# PowerManagement_uC_v2.net
KiCad netlist of a schematic drawn in Altium Designer
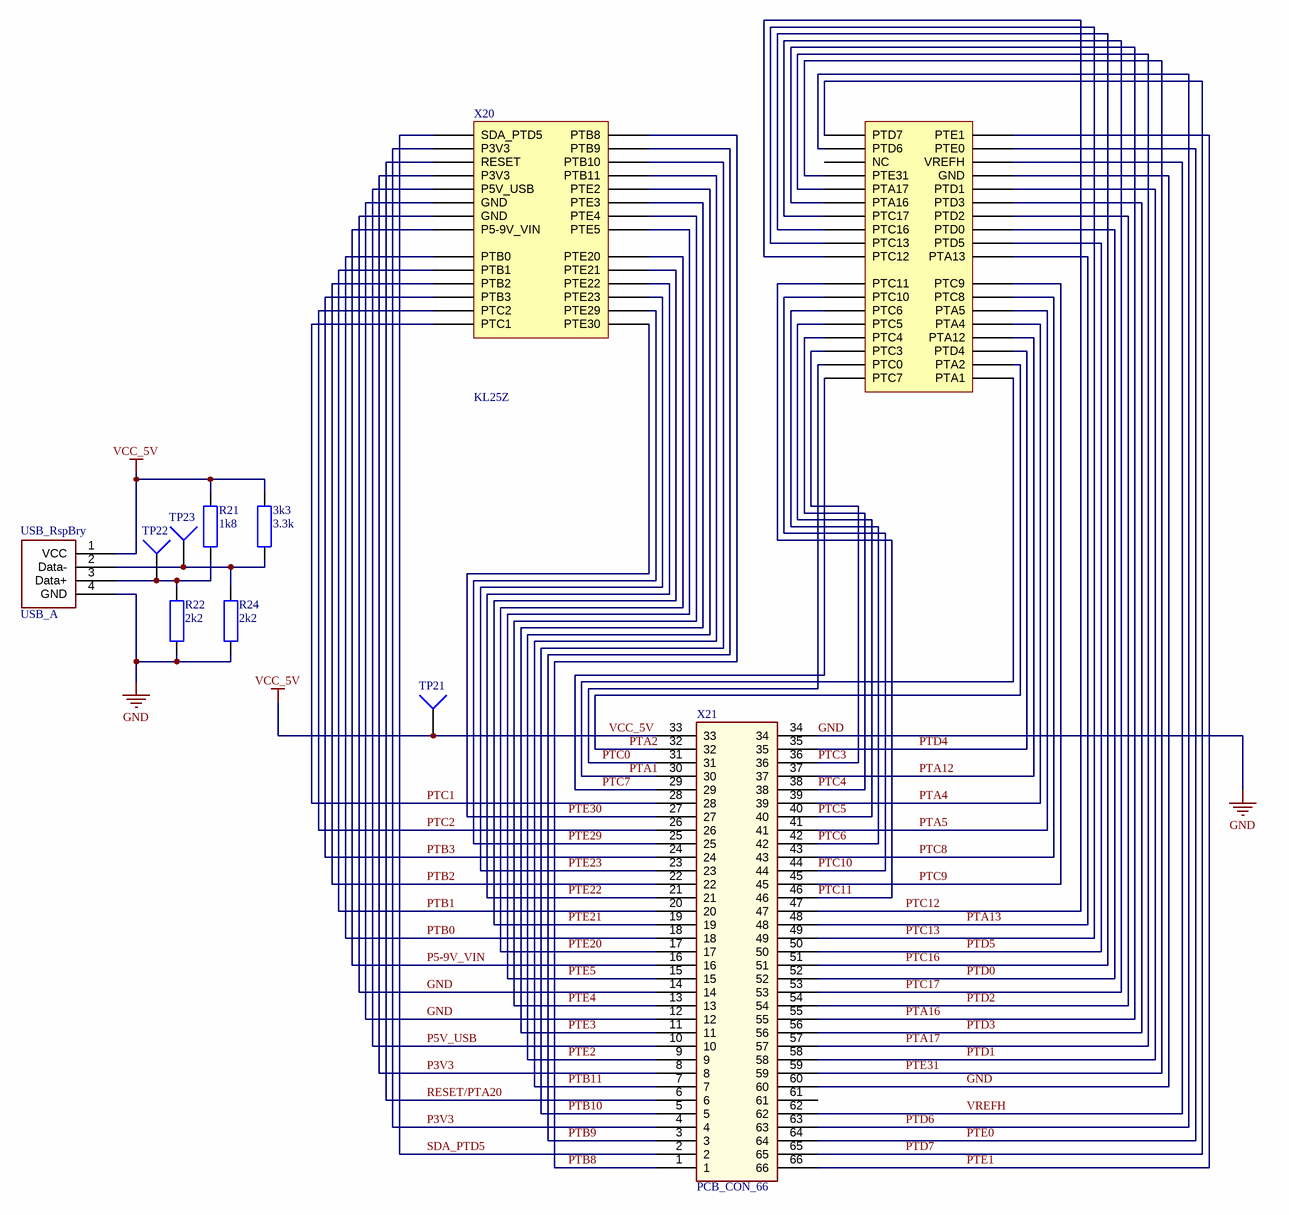
[diagram p0: PowerManagement_uC_v2.SchDoc]

(export (version "E")
  (design (tool "Eeschema 10.0.6"))
  (components
    (comp (ref "3k3")
      (value "3.3k")
      (footprint "0805")
      (description "Normaler Widerstand")
      (libsource (lib "SPICE_HSLU") (part "R?"))
    )
    (comp (ref "R21")
      (value "1k8")
      (footprint "0805")
      (description "Normaler Widerstand")
      (libsource (lib "SPICE_HSLU") (part "R?"))
    )
    (comp (ref "R22")
      (value "2k2")
      (footprint "0805")
      (description "Normaler Widerstand")
      (libsource (lib "SPICE_HSLU") (part "R?"))
    )
    (comp (ref "R24")
      (value "2k2")
      (footprint "0805")
      (description "Normaler Widerstand")
      (libsource (lib "SPICE_HSLU") (part "R?"))
    )
    (comp (ref "TP21")
      (value "~")
      (footprint "PIN1")
      (fields (field (name "PUBLISHER") "Altium Limited"))
      (libsource (lib "Miscellaneous Connectors") (part "Socket"))
    )
    (comp (ref "TP22")
      (value "~")
      (footprint "PIN1")
      (fields (field (name "PUBLISHER") "Altium Limited"))
      (libsource (lib "Miscellaneous Connectors") (part "Socket"))
    )
    (comp (ref "TP23")
      (value "~")
      (footprint "PIN1")
      (fields (field (name "PUBLISHER") "Altium Limited"))
      (libsource (lib "Miscellaneous Connectors") (part "Socket"))
    )
    (comp (ref "USB_RspBry") (value "USB_A") (footprint "USB_A") (libsource (lib "PREN2Lib") (part "USB_A")))
    (comp (ref "X20")
      (value "KL25Z")
      (footprint "Freedom KL25Z Headerarray")
      (description "FRDM KL25Z Shield")
      (libsource (lib "FreedomKL25Z") (part "Freedom KL25Z Header"))
    )
    (comp (ref "X21")
      (value "PCB_CON_66")
      (footprint "PCB_CON_66_PLUG")
      (description "Connects a PCB with another. This scheme is either jack or plug, depends on footprint")
      (libsource (lib "PREN2Lib") (part "PCB_CON_66"))
    )
  )
  (nets
    (net (code "1") (name "/P3V3") (class "Default")
      (node (ref "X20") (pin "3") (pinfunction "P3V3_3") (pintype "passive"))
      (node (ref "X20") (pin "7") (pinfunction "P3V3_7") (pintype "passive"))
      (node (ref "X21") (pin "4") (pinfunction "4_4") (pintype "passive"))
      (node (ref "X21") (pin "8") (pinfunction "8_8") (pintype "passive"))
    )
    (net (code "2") (name "/P5-9V_VIN") (class "Default")
      (node (ref "X20") (pin "15") (pinfunction "P5-9V_VIN_15") (pintype "passive"))
      (node (ref "X21") (pin "16") (pinfunction "16_16") (pintype "passive"))
    )
    (net (code "3") (name "/P5V_USB") (class "Default")
      (node (ref "X20") (pin "9") (pinfunction "P5V_USB_9") (pintype "passive"))
      (node (ref "X21") (pin "10") (pinfunction "10_10") (pintype "passive"))
    )
    (net (code "4") (name "/PTA1") (class "Default")
      (node (ref "X20") (pin "64") (pinfunction "PTA1_64") (pintype "passive"))
      (node (ref "X21") (pin "30") (pinfunction "30_30") (pintype "passive"))
    )
    (net (code "5") (name "/PTA2") (class "Default")
      (node (ref "X20") (pin "62") (pinfunction "PTA2_62") (pintype "passive"))
      (node (ref "X21") (pin "32") (pinfunction "32_32") (pintype "passive"))
    )
    (net (code "6") (name "/PTA4") (class "Default")
      (node (ref "X20") (pin "56") (pinfunction "PTA4_56") (pintype "passive"))
      (node (ref "X21") (pin "39") (pinfunction "39_39") (pintype "passive"))
    )
    (net (code "7") (name "/PTA5") (class "Default")
      (node (ref "X20") (pin "54") (pinfunction "PTA5_54") (pintype "passive"))
      (node (ref "X21") (pin "41") (pinfunction "41_41") (pintype "passive"))
    )
    (net (code "8") (name "/PTA12") (class "Default")
      (node (ref "X20") (pin "58") (pinfunction "PTA12_58") (pintype "passive"))
      (node (ref "X21") (pin "37") (pinfunction "37_37") (pintype "passive"))
    )
    (net (code "9") (name "/PTA13") (class "Default")
      (node (ref "X20") (pin "48") (pinfunction "PTA13_48") (pintype "passive"))
      (node (ref "X21") (pin "48") (pinfunction "48_48") (pintype "passive"))
    )
    (net (code "10") (name "/PTA16") (class "Default")
      (node (ref "X20") (pin "39") (pinfunction "PTA16_39") (pintype "passive"))
      (node (ref "X21") (pin "55") (pinfunction "55_55") (pintype "passive"))
    )
    (net (code "11") (name "/PTA17") (class "Default")
      (node (ref "X20") (pin "37") (pinfunction "PTA17_37") (pintype "passive"))
      (node (ref "X21") (pin "57") (pinfunction "57_57") (pintype "passive"))
    )
    (net (code "12") (name "/PTB0") (class "Default")
      (node (ref "X20") (pin "17") (pinfunction "PTB0_17") (pintype "passive"))
      (node (ref "X21") (pin "18") (pinfunction "18_18") (pintype "passive"))
    )
    (net (code "13") (name "/PTB1") (class "Default")
      (node (ref "X20") (pin "19") (pinfunction "PTB1_19") (pintype "passive"))
      (node (ref "X21") (pin "20") (pinfunction "20_20") (pintype "passive"))
    )
    (net (code "14") (name "/PTB2") (class "Default")
      (node (ref "X20") (pin "21") (pinfunction "PTB2_21") (pintype "passive"))
      (node (ref "X21") (pin "22") (pinfunction "22_22") (pintype "passive"))
    )
    (net (code "15") (name "/PTB3") (class "Default")
      (node (ref "X20") (pin "23") (pinfunction "PTB3_23") (pintype "passive"))
      (node (ref "X21") (pin "24") (pinfunction "24_24") (pintype "passive"))
    )
    (net (code "16") (name "/PTB8") (class "Default")
      (node (ref "X20") (pin "2") (pinfunction "PTB8_2") (pintype "passive"))
      (node (ref "X21") (pin "1") (pinfunction "1_1") (pintype "passive"))
    )
    (net (code "17") (name "/PTB9") (class "Default")
      (node (ref "X20") (pin "4") (pinfunction "PTB9_4") (pintype "passive"))
      (node (ref "X21") (pin "3") (pinfunction "3_3") (pintype "passive"))
    )
    (net (code "18") (name "/PTB10") (class "Default")
      (node (ref "X20") (pin "6") (pinfunction "PTB10_6") (pintype "passive"))
      (node (ref "X21") (pin "5") (pinfunction "5_5") (pintype "passive"))
    )
    (net (code "19") (name "/PTB11") (class "Default")
      (node (ref "X20") (pin "8") (pinfunction "PTB11_8") (pintype "passive"))
      (node (ref "X21") (pin "7") (pinfunction "7_7") (pintype "passive"))
    )
    (net (code "20") (name "/PTC0") (class "Default")
      (node (ref "X20") (pin "61") (pinfunction "PTC0_61") (pintype "passive"))
      (node (ref "X21") (pin "31") (pinfunction "31_31") (pintype "passive"))
    )
    (net (code "21") (name "/PTC1") (class "Default")
      (node (ref "X20") (pin "27") (pinfunction "PTC1_27") (pintype "passive"))
      (node (ref "X21") (pin "28") (pinfunction "28_28") (pintype "passive"))
    )
    (net (code "22") (name "/PTC2") (class "Default")
      (node (ref "X20") (pin "25") (pinfunction "PTC2_25") (pintype "passive"))
      (node (ref "X21") (pin "26") (pinfunction "26_26") (pintype "passive"))
    )
    (net (code "23") (name "/PTC3") (class "Default")
      (node (ref "X20") (pin "59") (pinfunction "PTC3_59") (pintype "passive"))
      (node (ref "X21") (pin "36") (pinfunction "36_36") (pintype "passive"))
    )
    (net (code "24") (name "/PTC4") (class "Default")
      (node (ref "X20") (pin "57") (pinfunction "PTC4_57") (pintype "passive"))
      (node (ref "X21") (pin "38") (pinfunction "38_38") (pintype "passive"))
    )
    (net (code "25") (name "/PTC5") (class "Default")
      (node (ref "X20") (pin "55") (pinfunction "PTC5_55") (pintype "passive"))
      (node (ref "X21") (pin "40") (pinfunction "40_40") (pintype "passive"))
    )
    (net (code "26") (name "/PTC6") (class "Default")
      (node (ref "X20") (pin "53") (pinfunction "PTC6_53") (pintype "passive"))
      (node (ref "X21") (pin "42") (pinfunction "42_42") (pintype "passive"))
    )
    (net (code "27") (name "/PTC7") (class "Default")
      (node (ref "X20") (pin "63") (pinfunction "PTC7_63") (pintype "passive"))
      (node (ref "X21") (pin "29") (pinfunction "29_29") (pintype "passive"))
    )
    (net (code "28") (name "/PTC8") (class "Default")
      (node (ref "X20") (pin "52") (pinfunction "PTC8_52") (pintype "passive"))
      (node (ref "X21") (pin "43") (pinfunction "43_43") (pintype "passive"))
    )
    (net (code "29") (name "/PTC9") (class "Default")
      (node (ref "X20") (pin "50") (pinfunction "PTC9_50") (pintype "passive"))
      (node (ref "X21") (pin "45") (pinfunction "45_45") (pintype "passive"))
    )
    (net (code "30") (name "/PTC10") (class "Default")
      (node (ref "X20") (pin "51") (pinfunction "PTC10_51") (pintype "passive"))
      (node (ref "X21") (pin "44") (pinfunction "44_44") (pintype "passive"))
    )
    (net (code "31") (name "/PTC11") (class "Default")
      (node (ref "X20") (pin "49") (pinfunction "PTC11_49") (pintype "passive"))
      (node (ref "X21") (pin "46") (pinfunction "46_46") (pintype "passive"))
    )
    (net (code "32") (name "/PTC12") (class "Default")
      (node (ref "X20") (pin "47") (pinfunction "PTC12_47") (pintype "passive"))
      (node (ref "X21") (pin "47") (pinfunction "47_47") (pintype "passive"))
    )
    (net (code "33") (name "/PTC13") (class "Default")
      (node (ref "X20") (pin "45") (pinfunction "PTC13_45") (pintype "passive"))
      (node (ref "X21") (pin "49") (pinfunction "49_49") (pintype "passive"))
    )
    (net (code "34") (name "/PTC16") (class "Default")
      (node (ref "X20") (pin "43") (pinfunction "PTC16_43") (pintype "passive"))
      (node (ref "X21") (pin "51") (pinfunction "51_51") (pintype "passive"))
    )
    (net (code "35") (name "/PTC17") (class "Default")
      (node (ref "X20") (pin "41") (pinfunction "PTC17_41") (pintype "passive"))
      (node (ref "X21") (pin "53") (pinfunction "53_53") (pintype "passive"))
    )
    (net (code "36") (name "/PTD0") (class "Default")
      (node (ref "X20") (pin "44") (pinfunction "PTD0_44") (pintype "passive"))
      (node (ref "X21") (pin "52") (pinfunction "52_52") (pintype "passive"))
    )
    (net (code "37") (name "/PTD1") (class "Default")
      (node (ref "X20") (pin "38") (pinfunction "PTD1_38") (pintype "passive"))
      (node (ref "X21") (pin "58") (pinfunction "58_58") (pintype "passive"))
    )
    (net (code "38") (name "/PTD2") (class "Default")
      (node (ref "X20") (pin "42") (pinfunction "PTD2_42") (pintype "passive"))
      (node (ref "X21") (pin "54") (pinfunction "54_54") (pintype "passive"))
    )
    (net (code "39") (name "/PTD3") (class "Default")
      (node (ref "X20") (pin "40") (pinfunction "PTD3_40") (pintype "passive"))
      (node (ref "X21") (pin "56") (pinfunction "56_56") (pintype "passive"))
    )
    (net (code "40") (name "/PTD4") (class "Default")
      (node (ref "X20") (pin "60") (pinfunction "PTD4_60") (pintype "passive"))
      (node (ref "X21") (pin "35") (pinfunction "35_35") (pintype "passive"))
    )
    (net (code "41") (name "/PTD5") (class "Default")
      (node (ref "X20") (pin "46") (pinfunction "PTD5_46") (pintype "passive"))
      (node (ref "X21") (pin "50") (pinfunction "50_50") (pintype "passive"))
    )
    (net (code "42") (name "/PTD6") (class "Default")
      (node (ref "X20") (pin "31") (pinfunction "PTD6_31") (pintype "passive"))
      (node (ref "X21") (pin "63") (pinfunction "63_63") (pintype "passive"))
    )
    (net (code "43") (name "/PTD7") (class "Default")
      (node (ref "X20") (pin "29") (pinfunction "PTD7_29") (pintype "passive"))
      (node (ref "X21") (pin "65") (pinfunction "65_65") (pintype "passive"))
    )
    (net (code "44") (name "/PTE0") (class "Default")
      (node (ref "X20") (pin "32") (pinfunction "PTE0_32") (pintype "passive"))
      (node (ref "X21") (pin "64") (pinfunction "64_64") (pintype "passive"))
    )
    (net (code "45") (name "/PTE1") (class "Default")
      (node (ref "X20") (pin "30") (pinfunction "PTE1_30") (pintype "passive"))
      (node (ref "X21") (pin "66") (pinfunction "66_66") (pintype "passive"))
    )
    (net (code "46") (name "/PTE2") (class "Default")
      (node (ref "X20") (pin "10") (pinfunction "PTE2_10") (pintype "passive"))
      (node (ref "X21") (pin "9") (pinfunction "9_9") (pintype "passive"))
    )
    (net (code "47") (name "/PTE3") (class "Default")
      (node (ref "X20") (pin "12") (pinfunction "PTE3_12") (pintype "passive"))
      (node (ref "X21") (pin "11") (pinfunction "11_11") (pintype "passive"))
    )
    (net (code "48") (name "/PTE4") (class "Default")
      (node (ref "X20") (pin "14") (pinfunction "PTE4_14") (pintype "passive"))
      (node (ref "X21") (pin "13") (pinfunction "13_13") (pintype "passive"))
    )
    (net (code "49") (name "/PTE5") (class "Default")
      (node (ref "X20") (pin "16") (pinfunction "PTE5_16") (pintype "passive"))
      (node (ref "X21") (pin "15") (pinfunction "15_15") (pintype "passive"))
    )
    (net (code "50") (name "/PTE20") (class "Default")
      (node (ref "X20") (pin "18") (pinfunction "PTE20_18") (pintype "passive"))
      (node (ref "X21") (pin "17") (pinfunction "17_17") (pintype "passive"))
    )
    (net (code "51") (name "/PTE21") (class "Default")
      (node (ref "X20") (pin "20") (pinfunction "PTE21_20") (pintype "passive"))
      (node (ref "X21") (pin "19") (pinfunction "19_19") (pintype "passive"))
    )
    (net (code "52") (name "/PTE22") (class "Default")
      (node (ref "X20") (pin "22") (pinfunction "PTE22_22") (pintype "passive"))
      (node (ref "X21") (pin "21") (pinfunction "21_21") (pintype "passive"))
    )
    (net (code "53") (name "/PTE23") (class "Default")
      (node (ref "X20") (pin "24") (pinfunction "PTE23_24") (pintype "passive"))
      (node (ref "X21") (pin "23") (pinfunction "23_23") (pintype "passive"))
    )
    (net (code "54") (name "/PTE29") (class "Default")
      (node (ref "X20") (pin "26") (pinfunction "PTE29_26") (pintype "passive"))
      (node (ref "X21") (pin "25") (pinfunction "25_25") (pintype "passive"))
    )
    (net (code "55") (name "/PTE30") (class "Default")
      (node (ref "X20") (pin "28") (pinfunction "PTE30_28") (pintype "passive"))
      (node (ref "X21") (pin "27") (pinfunction "27_27") (pintype "passive"))
    )
    (net (code "56") (name "/PTE31") (class "Default")
      (node (ref "X20") (pin "35") (pinfunction "PTE31_35") (pintype "passive"))
      (node (ref "X21") (pin "59") (pinfunction "59_59") (pintype "passive"))
    )
    (net (code "57") (name "/RESET{slash}PTA20") (class "Default")
      (node (ref "X20") (pin "5") (pinfunction "RESET_5") (pintype "passive"))
      (node (ref "X21") (pin "6") (pinfunction "6_6") (pintype "passive"))
    )
    (net (code "58") (name "/SDA_PTD5") (class "Default")
      (node (ref "X20") (pin "1") (pinfunction "SDA_PTD5_1") (pintype "passive"))
      (node (ref "X21") (pin "2") (pinfunction "2_2") (pintype "passive"))
    )
    (net (code "59") (name "/VREFH") (class "Default")
      (node (ref "X20") (pin "34") (pinfunction "VREFH_34") (pintype "passive"))
      (node (ref "X21") (pin "62") (pinfunction "62_62") (pintype "passive"))
    )
    (net (code "60") (name "GND") (class "Default")
      (node (ref "R22") (pin "1") (pintype "passive"))
      (node (ref "R24") (pin "1") (pintype "passive"))
      (node (ref "USB_RspBry") (pin "4") (pinfunction "GND_4") (pintype "passive"))
      (node (ref "X20") (pin "11") (pinfunction "GND_11") (pintype "passive"))
      (node (ref "X20") (pin "13") (pinfunction "GND_13") (pintype "passive"))
      (node (ref "X20") (pin "36") (pinfunction "GND_36") (pintype "passive"))
      (node (ref "X21") (pin "12") (pinfunction "12_12") (pintype "passive"))
      (node (ref "X21") (pin "14") (pinfunction "14_14") (pintype "passive"))
      (node (ref "X21") (pin "34") (pinfunction "34_34") (pintype "passive"))
      (node (ref "X21") (pin "60") (pinfunction "60_60") (pintype "passive"))
    )
    (net (code "61") (name "Net-(USB_RspBry-Data+)") (class "Default")
      (node (ref "R21") (pin "1") (pintype "passive"))
      (node (ref "R22") (pin "2") (pintype "passive"))
      (node (ref "TP22") (pin "1") (pinfunction "1_1") (pintype "passive"))
      (node (ref "USB_RspBry") (pin "3") (pinfunction "Data+_3") (pintype "passive"))
    )
    (net (code "62") (name "Net-(USB_RspBry-Data-)") (class "Default")
      (node (ref "3k3") (pin "1") (pintype "passive"))
      (node (ref "R24") (pin "2") (pintype "passive"))
      (node (ref "TP23") (pin "1") (pinfunction "1_1") (pintype "passive"))
      (node (ref "USB_RspBry") (pin "2") (pinfunction "Data-_2") (pintype "passive"))
    )
    (net (code "63") (name "VCC_5V") (class "Default")
      (node (ref "3k3") (pin "2") (pintype "passive"))
      (node (ref "R21") (pin "2") (pintype "passive"))
      (node (ref "TP21") (pin "1") (pinfunction "1_1") (pintype "passive"))
      (node (ref "USB_RspBry") (pin "1") (pinfunction "VCC_1") (pintype "passive"))
      (node (ref "X21") (pin "33") (pinfunction "33_33") (pintype "passive"))
    )
    (net (code "64") (name "unconnected-(X20-NC-Pad33)") (class "Default")
      (node (ref "X20") (pin "33") (pinfunction "NC_33") (pintype "passive"))
    )
    (net (code "65") (name "unconnected-(X21-Pad61)") (class "Default")
      (node (ref "X21") (pin "61") (pinfunction "61_61") (pintype "passive"))
    )
  )
)
